# AVR8-pin.net
KiCad netlist of a schematic drawn in EAGLE
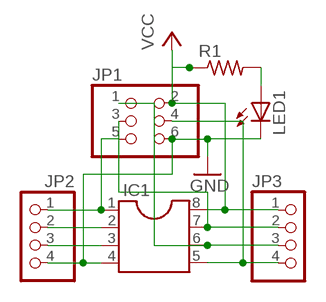
[diagram p0: schematic, sheet 1]

(export (version "E")
  (design (tool "Eeschema 10.0.6"))
  (components
    (comp (ref "IC1")
      (value "DIL8")
      (footprint "eagle-import:DIL08")
      (libsource (lib "eagle-import") (part "DIL8"))
    )
    (comp (ref "JP1")
      (value "PINHD-2X3")
      (footprint "eagle-import:2X03")
      (libsource (lib "eagle-import") (part "PINHD-2X3"))
    )
    (comp (ref "JP2")
      (value "PINHD-1X4")
      (footprint "eagle-import:1X04")
      (libsource (lib "eagle-import") (part "PINHD-1X4"))
    )
    (comp (ref "JP3")
      (value "PINHD-1X4")
      (footprint "eagle-import:1X04")
      (libsource (lib "eagle-import") (part "PINHD-1X4"))
    )
    (comp (ref "LED1")
      (value "LED3MM")
      (footprint "eagle-import:LED3MM")
      (libsource (lib "eagle-import") (part "LED3MM"))
    )
    (comp (ref "R1")
      (value "R-US_0207/2V")
      (footprint "eagle-import:0207_2V")
      (libsource (lib "eagle-import") (part "R-US_0207/2V"))
    )
  )
  (nets
    (net (code "1") (name "GND") (class "Default")
      (node (ref "IC1") (pin "4") (pinfunction "4_4") (pintype "passive"))
      (node (ref "JP1") (pin "6") (pinfunction "6_6") (pintype "passive"))
      (node (ref "JP2") (pin "4") (pinfunction "4_4") (pintype "passive"))
      (node (ref "LED1") (pin "K") (pinfunction "C_K") (pintype "passive"))
    )
    (net (code "2") (name "Net-(IC1-Pad1)") (class "Default")
      (node (ref "IC1") (pin "1") (pinfunction "1_1") (pintype "passive"))
      (node (ref "JP1") (pin "5") (pinfunction "5_5") (pintype "passive"))
      (node (ref "JP2") (pin "1") (pinfunction "1_1") (pintype "passive"))
    )
    (net (code "3") (name "Net-(IC1-Pad2)") (class "Default")
      (node (ref "IC1") (pin "2") (pinfunction "2_2") (pintype "passive"))
      (node (ref "JP2") (pin "2") (pinfunction "2_2") (pintype "passive"))
    )
    (net (code "4") (name "Net-(IC1-Pad3)") (class "Default")
      (node (ref "IC1") (pin "3") (pinfunction "3_3") (pintype "passive"))
      (node (ref "JP2") (pin "3") (pinfunction "3_3") (pintype "passive"))
    )
    (net (code "5") (name "Net-(IC1-Pad5)") (class "Default")
      (node (ref "IC1") (pin "5") (pinfunction "5_5") (pintype "passive"))
      (node (ref "JP1") (pin "4") (pinfunction "4_4") (pintype "passive"))
      (node (ref "JP3") (pin "4") (pinfunction "4_4") (pintype "passive"))
    )
    (net (code "6") (name "Net-(IC1-Pad6)") (class "Default")
      (node (ref "IC1") (pin "6") (pinfunction "6_6") (pintype "passive"))
      (node (ref "JP1") (pin "1") (pinfunction "1_1") (pintype "passive"))
      (node (ref "JP3") (pin "3") (pinfunction "3_3") (pintype "passive"))
    )
    (net (code "7") (name "Net-(IC1-Pad7)") (class "Default")
      (node (ref "IC1") (pin "7") (pinfunction "7_7") (pintype "passive"))
      (node (ref "JP1") (pin "3") (pinfunction "3_3") (pintype "passive"))
      (node (ref "JP3") (pin "2") (pinfunction "2_2") (pintype "passive"))
    )
    (net (code "8") (name "Net-(LED1-PadA)") (class "Default")
      (node (ref "LED1") (pin "A") (pinfunction "A_A") (pintype "passive"))
      (node (ref "R1") (pin "2") (pinfunction "2_2") (pintype "passive"))
    )
    (net (code "9") (name "VCC") (class "Default")
      (node (ref "IC1") (pin "8") (pinfunction "8_8") (pintype "passive"))
      (node (ref "JP1") (pin "2") (pinfunction "2_2") (pintype "passive"))
      (node (ref "JP3") (pin "1") (pinfunction "1_1") (pintype "passive"))
      (node (ref "R1") (pin "1") (pinfunction "1_1") (pintype "passive"))
    )
  )
)
